# heart.net
KiCad netlist of a schematic drawn in EAGLE
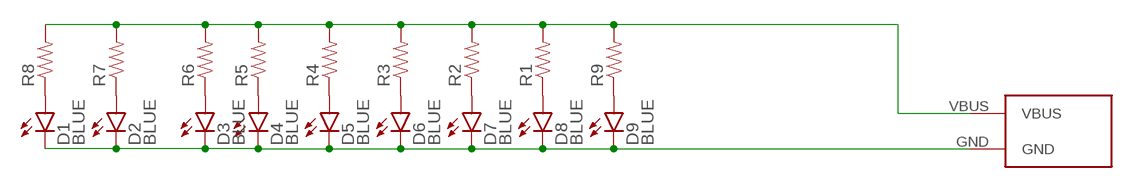
[diagram p0: schematic, sheet 1]

(export (version "E")
  (design (tool "Eeschema 10.0.6"))
  (components
    (comp (ref "D1")
      (value "BLUE")
      (footprint "eagle-import:LED-0603")
      (libsource (lib "eagle-import") (part "LED-BLUE0603"))
    )
    (comp (ref "D2")
      (value "BLUE")
      (footprint "eagle-import:LED-0603")
      (libsource (lib "eagle-import") (part "LED-BLUE0603"))
    )
    (comp (ref "D3")
      (value "BLUE")
      (footprint "eagle-import:LED-0603")
      (libsource (lib "eagle-import") (part "LED-BLUE0603"))
    )
    (comp (ref "D4")
      (value "BLUE")
      (footprint "eagle-import:LED-0603")
      (libsource (lib "eagle-import") (part "LED-BLUE0603"))
    )
    (comp (ref "D5")
      (value "BLUE")
      (footprint "eagle-import:LED-0603")
      (libsource (lib "eagle-import") (part "LED-BLUE0603"))
    )
    (comp (ref "D6")
      (value "BLUE")
      (footprint "eagle-import:LED-0603")
      (libsource (lib "eagle-import") (part "LED-BLUE0603"))
    )
    (comp (ref "D7")
      (value "BLUE")
      (footprint "eagle-import:LED-0603")
      (libsource (lib "eagle-import") (part "LED-BLUE0603"))
    )
    (comp (ref "D8")
      (value "BLUE")
      (footprint "eagle-import:LED-0603")
      (libsource (lib "eagle-import") (part "LED-BLUE0603"))
    )
    (comp (ref "D9")
      (value "BLUE")
      (footprint "eagle-import:LED-0603")
      (libsource (lib "eagle-import") (part "LED-BLUE0603"))
    )
    (comp (ref "R1")
      (value "RESISTOR0603-RES")
      (footprint "eagle-import:0603-RES")
      (libsource (lib "eagle-import") (part "RESISTOR0603-RES"))
    )
    (comp (ref "R2")
      (value "RESISTOR0603-RES")
      (footprint "eagle-import:0603-RES")
      (libsource (lib "eagle-import") (part "RESISTOR0603-RES"))
    )
    (comp (ref "R3")
      (value "RESISTOR0603-RES")
      (footprint "eagle-import:0603-RES")
      (libsource (lib "eagle-import") (part "RESISTOR0603-RES"))
    )
    (comp (ref "R4")
      (value "RESISTOR0603-RES")
      (footprint "eagle-import:0603-RES")
      (libsource (lib "eagle-import") (part "RESISTOR0603-RES"))
    )
    (comp (ref "R5")
      (value "RESISTOR0603-RES")
      (footprint "eagle-import:0603-RES")
      (libsource (lib "eagle-import") (part "RESISTOR0603-RES"))
    )
    (comp (ref "R6")
      (value "RESISTOR0603-RES")
      (footprint "eagle-import:0603-RES")
      (libsource (lib "eagle-import") (part "RESISTOR0603-RES"))
    )
    (comp (ref "R7")
      (value "RESISTOR0603-RES")
      (footprint "eagle-import:0603-RES")
      (libsource (lib "eagle-import") (part "RESISTOR0603-RES"))
    )
    (comp (ref "R8")
      (value "RESISTOR0603-RES")
      (footprint "eagle-import:0603-RES")
      (libsource (lib "eagle-import") (part "RESISTOR0603-RES"))
    )
    (comp (ref "R9")
      (value "RESISTOR0603-RES")
      (footprint "eagle-import:0603-RES")
      (libsource (lib "eagle-import") (part "RESISTOR0603-RES"))
    )
    (comp (ref "U$1")
      (value "USBMALEA")
      (footprint "eagle-import:USBMALEA")
      (libsource (lib "eagle-import") (part "USBMALEA"))
    )
  )
  (nets
    (net (code "1") (name "Net-(D1-PadA)") (class "Default")
      (node (ref "D1") (pin "A") (pinfunction "A_A") (pintype "passive"))
      (node (ref "R8") (pin "1") (pinfunction "1_1") (pintype "passive"))
    )
    (net (code "2") (name "Net-(D1-PadC)") (class "Default")
      (node (ref "D1") (pin "C") (pinfunction "C_C") (pintype "passive"))
      (node (ref "D2") (pin "C") (pinfunction "C_C") (pintype "passive"))
      (node (ref "D3") (pin "C") (pinfunction "C_C") (pintype "passive"))
      (node (ref "D4") (pin "C") (pinfunction "C_C") (pintype "passive"))
      (node (ref "D5") (pin "C") (pinfunction "C_C") (pintype "passive"))
      (node (ref "D6") (pin "C") (pinfunction "C_C") (pintype "passive"))
      (node (ref "D7") (pin "C") (pinfunction "C_C") (pintype "passive"))
      (node (ref "D8") (pin "C") (pinfunction "C_C") (pintype "passive"))
      (node (ref "D9") (pin "C") (pinfunction "C_C") (pintype "passive"))
      (node (ref "U$1") (pin "GND") (pinfunction "GND_GND") (pintype "bidirectional"))
    )
    (net (code "3") (name "Net-(D2-PadA)") (class "Default")
      (node (ref "D2") (pin "A") (pinfunction "A_A") (pintype "passive"))
      (node (ref "R7") (pin "1") (pinfunction "1_1") (pintype "passive"))
    )
    (net (code "4") (name "Net-(D3-PadA)") (class "Default")
      (node (ref "D3") (pin "A") (pinfunction "A_A") (pintype "passive"))
      (node (ref "R6") (pin "1") (pinfunction "1_1") (pintype "passive"))
    )
    (net (code "5") (name "Net-(D4-PadA)") (class "Default")
      (node (ref "D4") (pin "A") (pinfunction "A_A") (pintype "passive"))
      (node (ref "R5") (pin "1") (pinfunction "1_1") (pintype "passive"))
    )
    (net (code "6") (name "Net-(D5-PadA)") (class "Default")
      (node (ref "D5") (pin "A") (pinfunction "A_A") (pintype "passive"))
      (node (ref "R4") (pin "1") (pinfunction "1_1") (pintype "passive"))
    )
    (net (code "7") (name "Net-(D6-PadA)") (class "Default")
      (node (ref "D6") (pin "A") (pinfunction "A_A") (pintype "passive"))
      (node (ref "R3") (pin "1") (pinfunction "1_1") (pintype "passive"))
    )
    (net (code "8") (name "Net-(D7-PadA)") (class "Default")
      (node (ref "D7") (pin "A") (pinfunction "A_A") (pintype "passive"))
      (node (ref "R2") (pin "1") (pinfunction "1_1") (pintype "passive"))
    )
    (net (code "9") (name "Net-(D8-PadA)") (class "Default")
      (node (ref "D8") (pin "A") (pinfunction "A_A") (pintype "passive"))
      (node (ref "R1") (pin "1") (pinfunction "1_1") (pintype "passive"))
    )
    (net (code "10") (name "Net-(D9-PadA)") (class "Default")
      (node (ref "D9") (pin "A") (pinfunction "A_A") (pintype "passive"))
      (node (ref "R9") (pin "1") (pinfunction "1_1") (pintype "passive"))
    )
    (net (code "11") (name "Net-(R1-Pad2)") (class "Default")
      (node (ref "R1") (pin "2") (pinfunction "2_2") (pintype "passive"))
      (node (ref "R2") (pin "2") (pinfunction "2_2") (pintype "passive"))
      (node (ref "R3") (pin "2") (pinfunction "2_2") (pintype "passive"))
      (node (ref "R4") (pin "2") (pinfunction "2_2") (pintype "passive"))
      (node (ref "R5") (pin "2") (pinfunction "2_2") (pintype "passive"))
      (node (ref "R6") (pin "2") (pinfunction "2_2") (pintype "passive"))
      (node (ref "R7") (pin "2") (pinfunction "2_2") (pintype "passive"))
      (node (ref "R8") (pin "2") (pinfunction "2_2") (pintype "passive"))
      (node (ref "R9") (pin "2") (pinfunction "2_2") (pintype "passive"))
      (node (ref "U$1") (pin "VBUS") (pinfunction "VBUS_VBUS") (pintype "bidirectional"))
    )
  )
)
